# Lora_GPS_Shield_v1_3.net
KiCad netlist of a schematic drawn in EAGLE
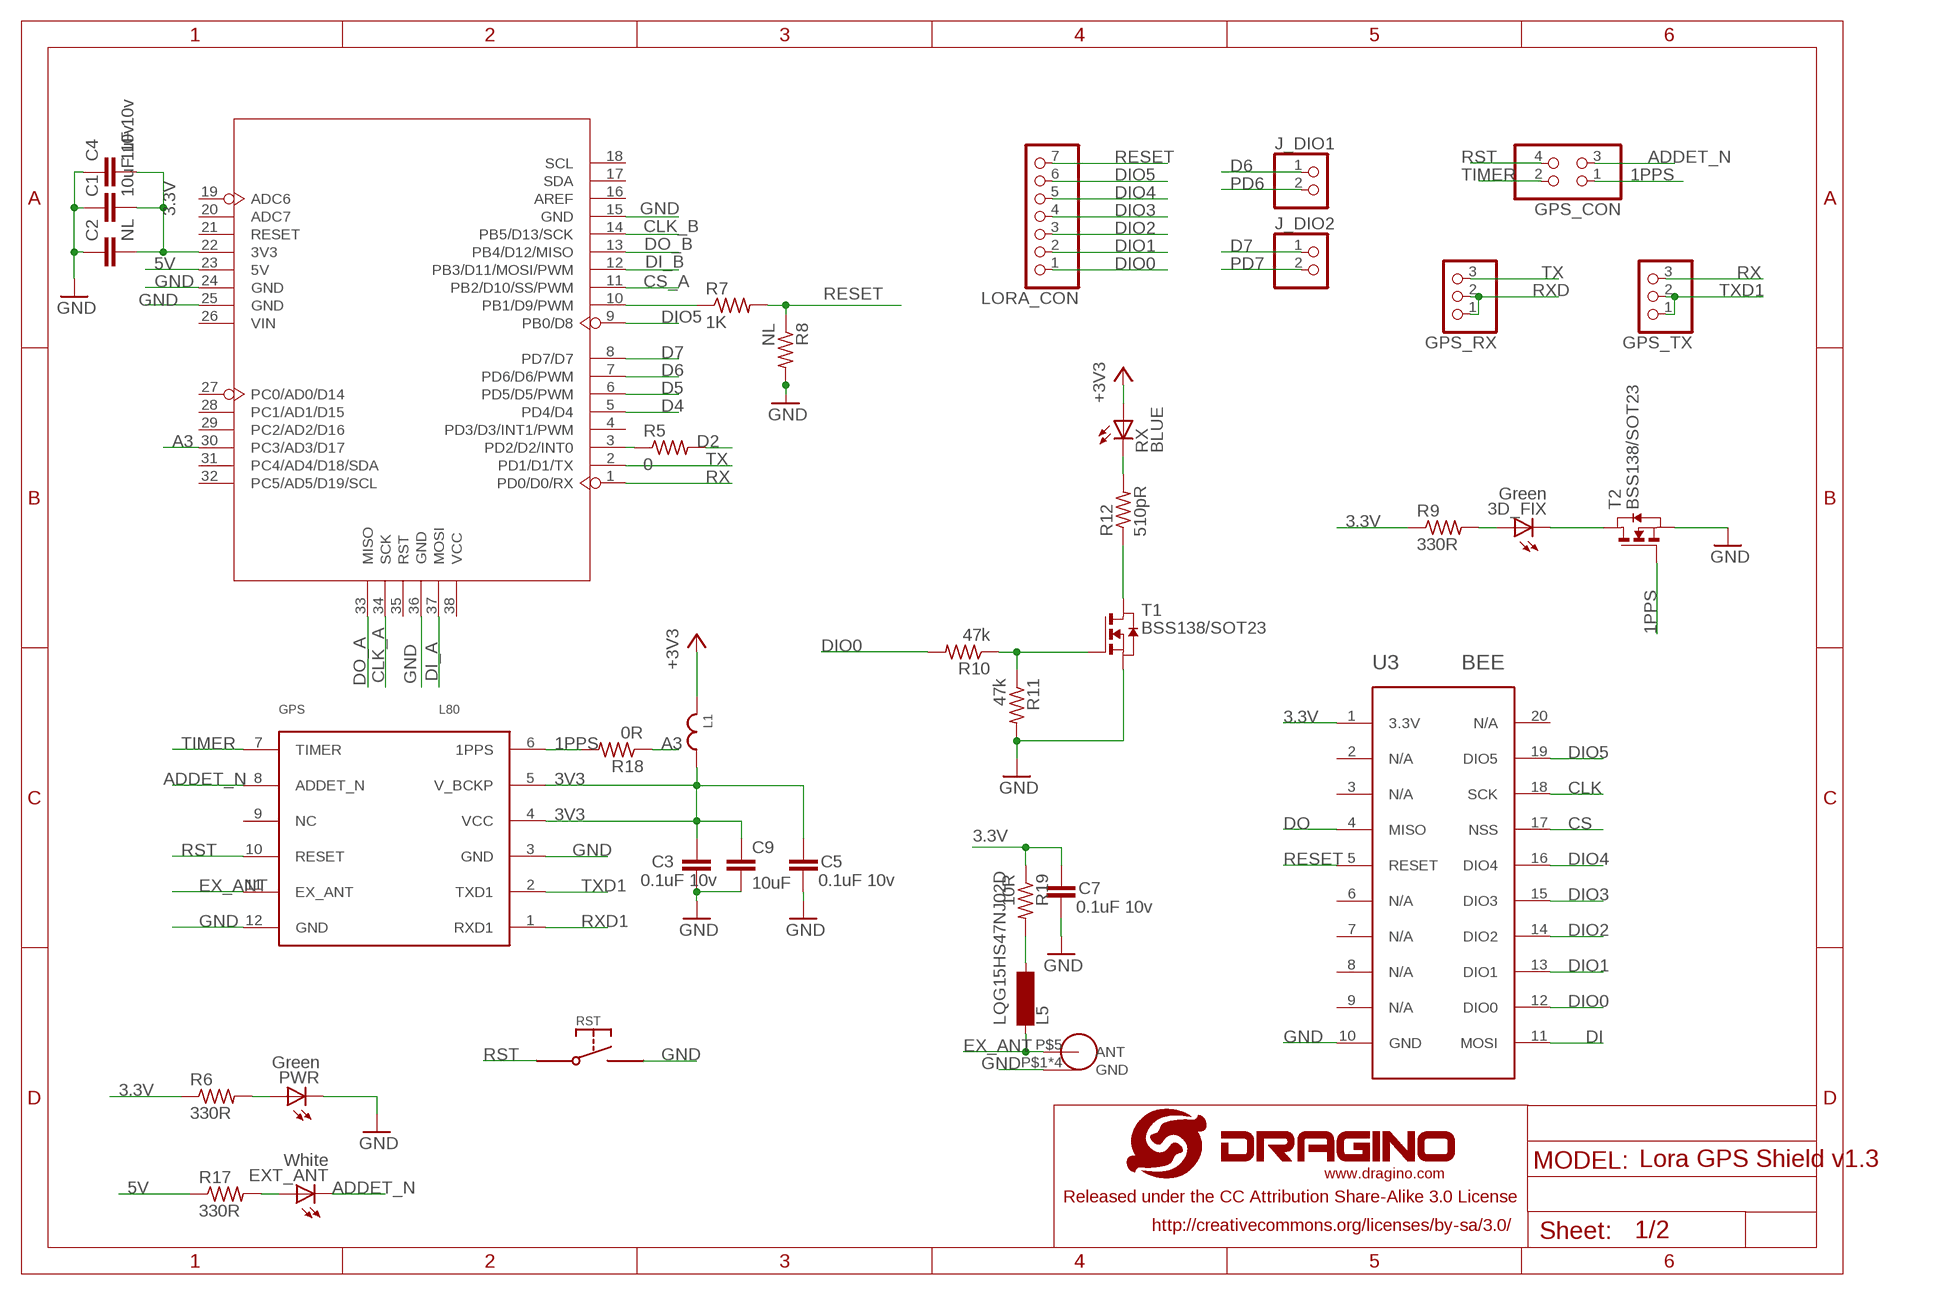
[diagram p0: schematic, sheet 1]
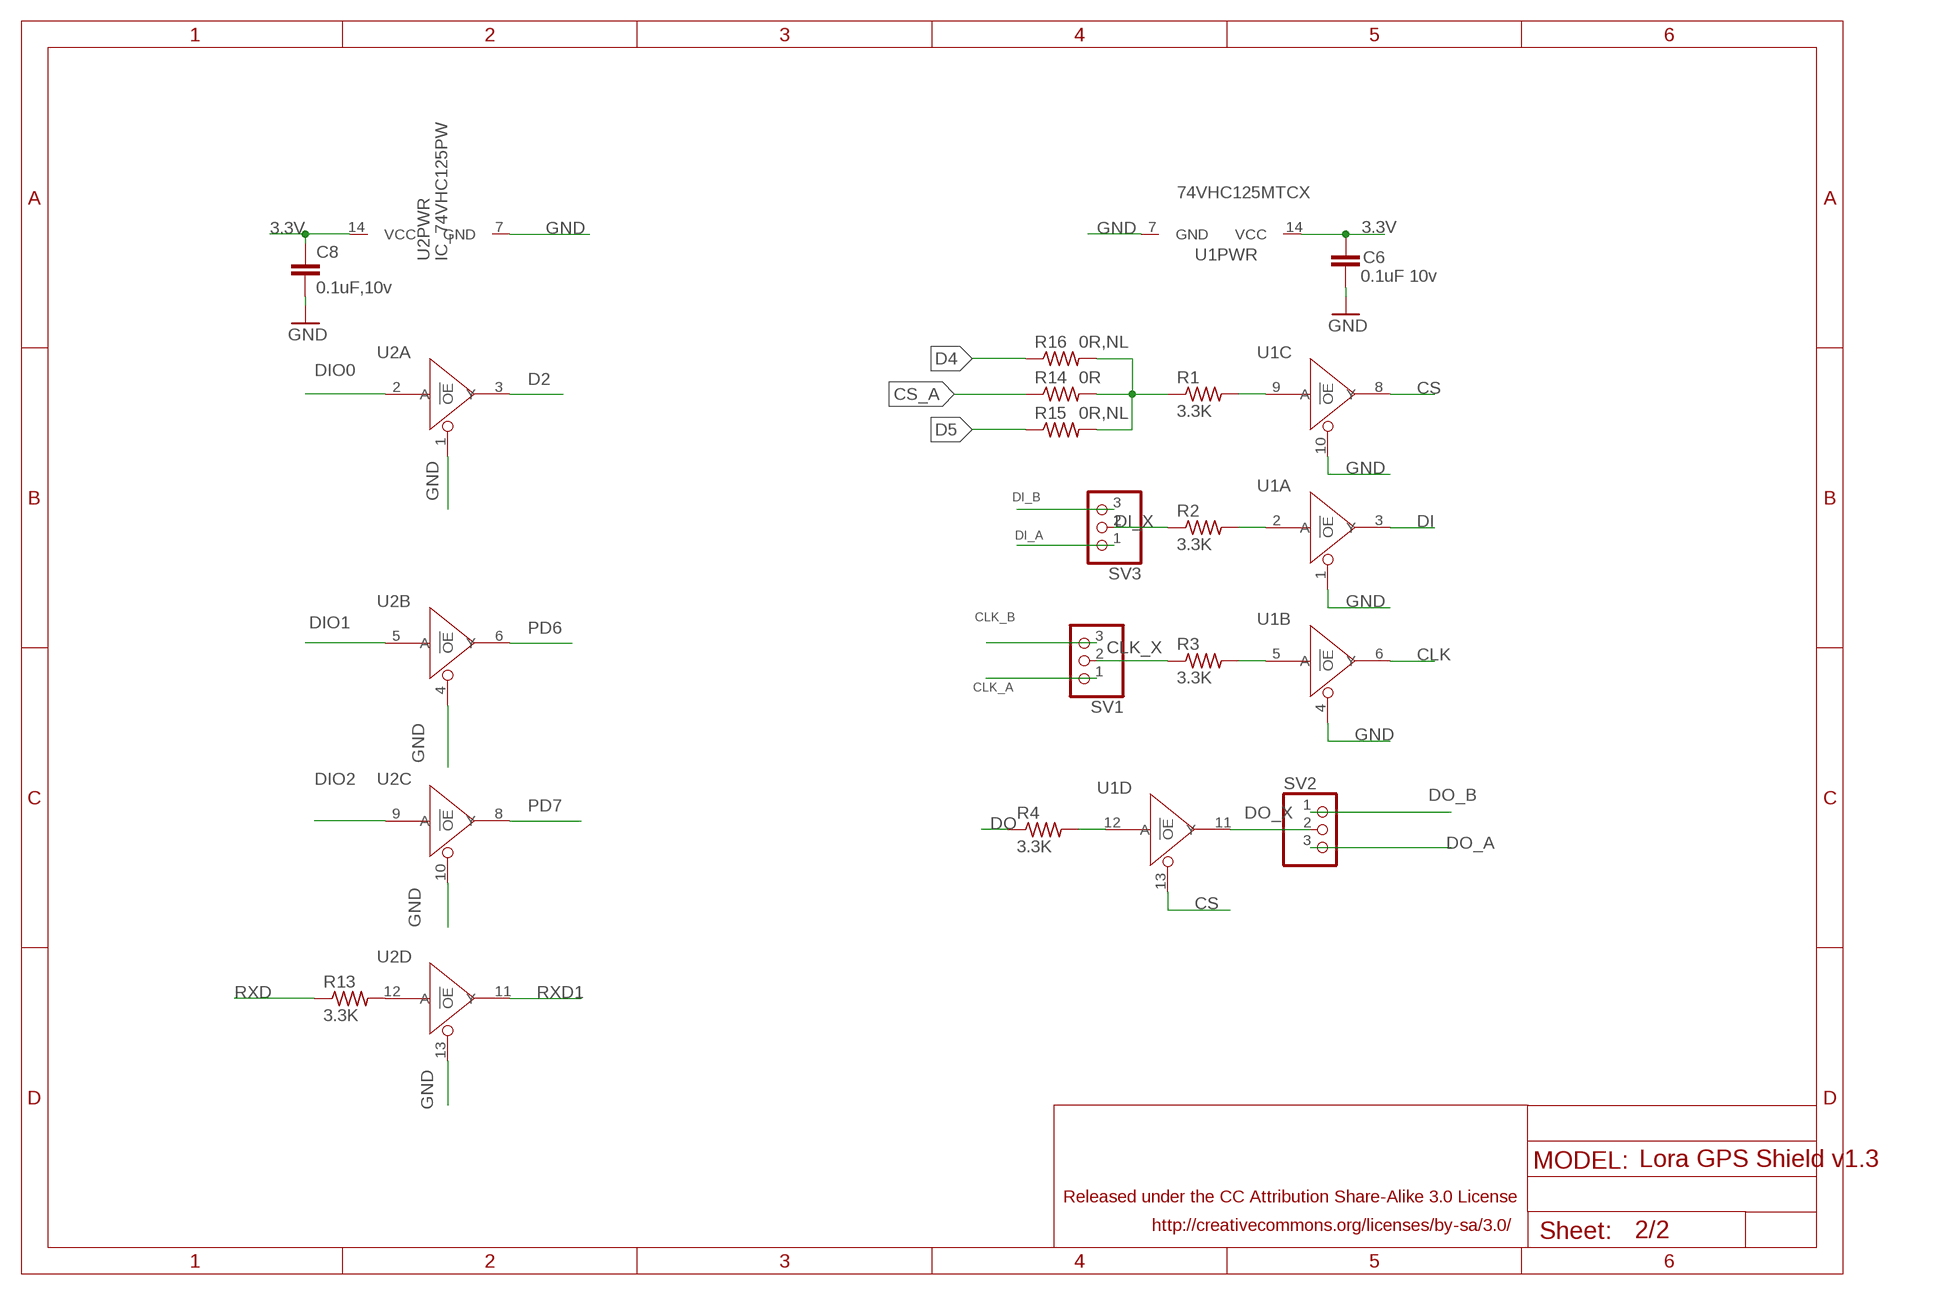
[diagram p1: schematic, sheet 2]

(export (version "E")
  (design (tool "Eeschema 10.0.6"))
  (components
    (comp (ref "C6")
      (value "0.1uF 10v")
      (footprint "eagle-import:C0402")
      (libsource (lib "eagle-import") (part "C-EUC0402"))
    )
    (comp (ref "C8")
      (value "0.1uF,10v")
      (footprint "eagle-import:C0402")
      (libsource (lib "eagle-import") (part "C-EUC0402"))
    )
    (comp (ref "R1")
      (value "3.3K")
      (footprint "eagle-import:R0402")
      (libsource (lib "eagle-import") (part "R-US_R0402"))
    )
    (comp (ref "R2")
      (value "3.3K")
      (footprint "eagle-import:R0402")
      (libsource (lib "eagle-import") (part "R-US_R0402"))
    )
    (comp (ref "R3")
      (value "3.3K")
      (footprint "eagle-import:R0402")
      (libsource (lib "eagle-import") (part "R-US_R0402"))
    )
    (comp (ref "R4")
      (value "3.3K")
      (footprint "eagle-import:R0402")
      (libsource (lib "eagle-import") (part "R-US_R0402"))
    )
    (comp (ref "R13")
      (value "3.3K")
      (footprint "eagle-import:R0402")
      (libsource (lib "eagle-import") (part "R-US_R0402"))
    )
    (comp (ref "R14")
      (value "0R")
      (footprint "eagle-import:R0603")
      (libsource (lib "eagle-import") (part "R-US_R0603"))
    )
    (comp (ref "R15")
      (value "0R,NL")
      (footprint "eagle-import:R0603")
      (libsource (lib "eagle-import") (part "R-US_R0603"))
    )
    (comp (ref "R16")
      (value "0R,NL")
      (footprint "eagle-import:R0603")
      (libsource (lib "eagle-import") (part "R-US_R0603"))
    )
    (comp (ref "SV1")
      (value "PINHD-1X31X3_S")
      (footprint "eagle-import:1X03")
      (libsource (lib "eagle-import") (part "PINHD-1X31X3_S"))
    )
    (comp (ref "SV2")
      (value "PINHD-1X3")
      (footprint "eagle-import:1X03")
      (libsource (lib "eagle-import") (part "PINHD-1X3"))
    )
    (comp (ref "SV3")
      (value "PINHD-1X3")
      (footprint "eagle-import:1X03")
      (libsource (lib "eagle-import") (part "PINHD-1X3"))
    )
    (comp (ref "U1")
      (value "74VHC125MTCX")
      (footprint "eagle-import:TSSOP14")
      (libsource (lib "eagle-import") (part "IC_74V125PWHC"))
    )
    (comp (ref "U2")
      (value "IC_74VHC125PW")
      (footprint "eagle-import:IC_TSSOP14")
      (libsource (lib "eagle-import") (part "IC_74V125PWHC"))
    )
    (comp (ref "3D_FIX")
      (value "Green")
      (footprint "eagle-import:CHIPLED_0603")
      (libsource (lib "eagle-import") (part "LEDCHIPLED_0603"))
    )
    (comp (ref "C1")
      (value "10uF 10v")
      (footprint "eagle-import:C0805")
      (libsource (lib "eagle-import") (part "C-EUC0805"))
    )
    (comp (ref "C2")
      (value "NL")
      (footprint "eagle-import:C0402")
      (libsource (lib "eagle-import") (part "C-EUC0402"))
    )
    (comp (ref "C3")
      (value "0.1uF 10v")
      (footprint "eagle-import:C0402")
      (libsource (lib "eagle-import") (part "C-EUC0402"))
    )
    (comp (ref "C4")
      (value "1uF 10v")
      (footprint "eagle-import:C0402")
      (libsource (lib "eagle-import") (part "C-EUC0402"))
    )
    (comp (ref "C5")
      (value "0.1uF 10v")
      (footprint "eagle-import:C0402")
      (libsource (lib "eagle-import") (part "C-EUC0402"))
    )
    (comp (ref "C7")
      (value "0.1uF 10v")
      (footprint "eagle-import:C0402")
      (libsource (lib "eagle-import") (part "C-EUC0402"))
    )
    (comp (ref "C9")
      (value "10uF")
      (footprint "eagle-import:C0805")
      (libsource (lib "eagle-import") (part "C-EUC0805"))
    )
    (comp (ref "EXT_ANT")
      (value "White")
      (footprint "eagle-import:DRAGINO_CHIPLED_0603")
      (libsource (lib "eagle-import") (part "DRAGINO_LEDCHIPLED_0603"))
    )
    (comp (ref "GPS")
      (value "L80")
      (footprint "eagle-import:L80")
      (libsource (lib "eagle-import") (part "L80"))
    )
    (comp (ref "GPS_ANT")
      (value "NL")
      (footprint "eagle-import:SMA-KE")
      (libsource (lib "eagle-import") (part "SMA-KE"))
    )
    (comp (ref "GPS_CON")
      (value "PINHD-2X2")
      (footprint "eagle-import:2X02")
      (libsource (lib "eagle-import") (part "PINHD-2X2"))
    )
    (comp (ref "GPS_RX")
      (value "PINHD-1X3")
      (footprint "eagle-import:1X03")
      (libsource (lib "eagle-import") (part "PINHD-1X3"))
    )
    (comp (ref "GPS_TX")
      (value "PINHD-1X3")
      (footprint "eagle-import:1X03")
      (libsource (lib "eagle-import") (part "PINHD-1X3"))
    )
    (comp (ref "J_DIO1")
      (value "PINHD-1X21X2_S")
      (footprint "eagle-import:1X02")
      (libsource (lib "eagle-import") (part "PINHD-1X21X2_S"))
    )
    (comp (ref "J_DIO2")
      (value "PINHD-1X2")
      (footprint "eagle-import:1X02")
      (libsource (lib "eagle-import") (part "PINHD-1X2"))
    )
    (comp (ref "L1")
      (value "JLC-PZ2012D800-3R0TF")
      (footprint "eagle-import:C0805")
      (libsource (lib "eagle-import") (part "BEADS0805"))
    )
    (comp (ref "L5")
      (value "LQG15HS47NJ02D")
      (footprint "eagle-import:L-0402")
      (libsource (lib "eagle-import") (part "L"))
    )
    (comp (ref "LORA_CON")
      (value "PINHD-1X71X7_S")
      (footprint "eagle-import:1X07")
      (libsource (lib "eagle-import") (part "PINHD-1X71X7_S"))
    )
    (comp (ref "PWR")
      (value "Green")
      (footprint "eagle-import:DRAGINO_CHIPLED_0603")
      (libsource (lib "eagle-import") (part "DRAGINO_LEDCHIPLED_0603"))
    )
    (comp (ref "R5")
      (value "0")
      (footprint "eagle-import:R0402")
      (libsource (lib "eagle-import") (part "R-US_R0402"))
    )
    (comp (ref "R6")
      (value "330R")
      (footprint "eagle-import:R0402")
      (libsource (lib "eagle-import") (part "R-US_R0402"))
    )
    (comp (ref "R7")
      (value "1K")
      (footprint "eagle-import:R0402")
      (libsource (lib "eagle-import") (part "R-US_R0402"))
    )
    (comp (ref "R8")
      (value "NL")
      (footprint "eagle-import:R0402")
      (libsource (lib "eagle-import") (part "R-US_R0402"))
    )
    (comp (ref "R9")
      (value "330R")
      (footprint "eagle-import:R0402")
      (libsource (lib "eagle-import") (part "R-US_R0402"))
    )
    (comp (ref "R10")
      (value "47k")
      (footprint "eagle-import:R0402")
      (libsource (lib "eagle-import") (part "R-US_R0402"))
    )
    (comp (ref "R11")
      (value "47k")
      (footprint "eagle-import:R0402")
      (libsource (lib "eagle-import") (part "R-US_R0402"))
    )
    (comp (ref "R12")
      (value "510pR")
      (footprint "eagle-import:R0402")
      (libsource (lib "eagle-import") (part "R-US_R0402"))
    )
    (comp (ref "R17")
      (value "330R")
      (footprint "eagle-import:R0402")
      (libsource (lib "eagle-import") (part "R-US_R0402"))
    )
    (comp (ref "R18")
      (value "0R")
      (footprint "eagle-import:M0805")
      (libsource (lib "eagle-import") (part "R-US_M0805"))
    )
    (comp (ref "R19")
      (value "10R")
      (footprint "eagle-import:R0402")
      (libsource (lib "eagle-import") (part "R-US_R0402"))
    )
    (comp (ref "RST")
      (value "SWITCHTS-017")
      (footprint "eagle-import:TS-017")
      (libsource (lib "eagle-import") (part "SWITCHTS-017"))
    )
    (comp (ref "RX")
      (value "BLUE")
      (footprint "eagle-import:CHIPLED_0603")
      (libsource (lib "eagle-import") (part "dragino-passive_LEDCHIPLED_0603"))
    )
    (comp (ref "T1")
      (value "BSS138/SOT23")
      (footprint "eagle-import:SOT-23")
      (libsource (lib "eagle-import") (part "NMOSFET-SOT23"))
    )
    (comp (ref "T2")
      (value "BSS138/SOT23")
      (footprint "eagle-import:SOT-23")
      (libsource (lib "eagle-import") (part "NMOSFET-SOT23"))
    )
    (comp (ref "U$1")
      (value "LOGO-NEW")
      (footprint "eagle-import:LOGO-SILK-NEW")
      (libsource (lib "eagle-import") (part "LOGO-NEW"))
    )
    (comp (ref "U3")
      (value "BEE")
      (footprint "eagle-import:LORA")
      (libsource (lib "eagle-import") (part "LORAHAT_S"))
    )
    (comp (ref "U5")
      (value "MOUDLE_ARDUINO-38PMOUDLE_ARDUINO-38P_L")
      (footprint "eagle-import:MOUDLE_ARDUINO-38P_L")
      (libsource (lib "eagle-import") (part "MOUDLE_ARDUINO-38PMOUDLE_ARDUINO-38P_L"))
    )
  )
  (nets
    (net (code "1") (name "1PPS") (class "Default")
      (node (ref "GPS") (pin "6") (pinfunction "1PPS_6") (pintype "bidirectional"))
      (node (ref "GPS_CON") (pin "1") (pinfunction "1_1") (pintype "passive"))
      (node (ref "R18") (pin "2") (pinfunction "2_2") (pintype "passive"))
      (node (ref "T2") (pin "3") (pinfunction "G_3") (pintype "passive"))
    )
    (net (code "2") (name "3.3V") (class "Default")
      (node (ref "C1") (pin "2") (pinfunction "2_2") (pintype "passive"))
      (node (ref "C2") (pin "2") (pinfunction "2_2") (pintype "passive"))
      (node (ref "C4") (pin "2") (pinfunction "2_2") (pintype "passive"))
      (node (ref "C6") (pin "2") (pinfunction "2_2") (pintype "passive"))
      (node (ref "C7") (pin "2") (pinfunction "2_2") (pintype "passive"))
      (node (ref "C8") (pin "1") (pinfunction "1_1") (pintype "passive"))
      (node (ref "L1") (pin "1") (pinfunction "P$1_1") (pintype "bidirectional"))
      (node (ref "R19") (pin "1") (pinfunction "1_1") (pintype "passive"))
      (node (ref "R6") (pin "1") (pinfunction "1_1") (pintype "passive"))
      (node (ref "R9") (pin "1") (pinfunction "1_1") (pintype "passive"))
      (node (ref "RX") (pin "A") (pinfunction "A_A") (pintype "passive"))
      (node (ref "U1") (pin "14") (pinfunction "VCC_14") (pintype "power_in"))
      (node (ref "U2") (pin "14") (pinfunction "VCC_14") (pintype "power_in"))
      (node (ref "U3") (pin "1") (pinfunction "3.3V_1") (pintype "bidirectional"))
      (node (ref "U5") (pin "22") (pinfunction "3V3_22") (pintype "bidirectional"))
    )
    (net (code "3") (name "3V3") (class "Default")
      (node (ref "C3") (pin "2") (pinfunction "2_2") (pintype "passive"))
      (node (ref "C5") (pin "2") (pinfunction "2_2") (pintype "passive"))
      (node (ref "C9") (pin "1") (pinfunction "1_1") (pintype "passive"))
      (node (ref "GPS") (pin "4") (pinfunction "VCC_4") (pintype "bidirectional"))
      (node (ref "GPS") (pin "5") (pinfunction "V_BCKP_5") (pintype "bidirectional"))
      (node (ref "L1") (pin "2") (pinfunction "P$2_2") (pintype "bidirectional"))
    )
    (net (code "4") (name "5V") (class "Default")
      (node (ref "R17") (pin "1") (pinfunction "1_1") (pintype "passive"))
      (node (ref "U5") (pin "23") (pinfunction "5V_23") (pintype "bidirectional"))
    )
    (net (code "5") (name "A3") (class "Default")
      (node (ref "R18") (pin "1") (pinfunction "1_1") (pintype "passive"))
      (node (ref "U5") (pin "30") (pinfunction "PC3/AD3/D17_30") (pintype "bidirectional"))
    )
    (net (code "6") (name "ADDET_N") (class "Default")
      (node (ref "EXT_ANT") (pin "C") (pinfunction "C_C") (pintype "passive"))
      (node (ref "GPS") (pin "8") (pinfunction "ADDET_N_8") (pintype "bidirectional"))
      (node (ref "GPS_CON") (pin "3") (pinfunction "3_3") (pintype "passive"))
    )
    (net (code "7") (name "CLK") (class "Default")
      (node (ref "U1") (pin "6") (pinfunction "Y_6") (pintype "bidirectional"))
      (node (ref "U3") (pin "18") (pinfunction "SCK_18") (pintype "bidirectional"))
    )
    (net (code "8") (name "CLK_A") (class "Default")
      (node (ref "SV1") (pin "1") (pinfunction "1_1") (pintype "passive"))
      (node (ref "U5") (pin "34") (pinfunction "SCK_34") (pintype "bidirectional"))
    )
    (net (code "9") (name "CLK_B") (class "Default")
      (node (ref "SV1") (pin "3") (pinfunction "3_3") (pintype "passive"))
      (node (ref "U5") (pin "14") (pinfunction "PB5/D13/SCK_14") (pintype "bidirectional"))
    )
    (net (code "10") (name "CLK_X") (class "Default")
      (node (ref "R3") (pin "1") (pinfunction "1_1") (pintype "passive"))
      (node (ref "SV1") (pin "2") (pinfunction "2_2") (pintype "passive"))
    )
    (net (code "11") (name "CS") (class "Default")
      (node (ref "U1") (pin "13") (pinfunction "~{OE}_13") (pintype "bidirectional"))
      (node (ref "U1") (pin "8") (pinfunction "Y_8") (pintype "bidirectional"))
      (node (ref "U3") (pin "17") (pinfunction "NSS_17") (pintype "bidirectional"))
    )
    (net (code "12") (name "CS_A") (class "Default")
      (node (ref "R14") (pin "1") (pinfunction "1_1") (pintype "passive"))
      (node (ref "U5") (pin "11") (pinfunction "PB2/D10/SS/PWM_11") (pintype "bidirectional"))
    )
    (net (code "13") (name "D2") (class "Default")
      (node (ref "R5") (pin "2") (pinfunction "2_2") (pintype "passive"))
      (node (ref "U2") (pin "3") (pinfunction "Y_3") (pintype "bidirectional"))
    )
    (net (code "14") (name "D4") (class "Default")
      (node (ref "R16") (pin "1") (pinfunction "1_1") (pintype "passive"))
      (node (ref "U5") (pin "5") (pinfunction "PD4/D4_5") (pintype "bidirectional"))
    )
    (net (code "15") (name "D5") (class "Default")
      (node (ref "R15") (pin "1") (pinfunction "1_1") (pintype "passive"))
      (node (ref "U5") (pin "6") (pinfunction "PD5/D5/PWM_6") (pintype "bidirectional"))
    )
    (net (code "16") (name "D6") (class "Default")
      (node (ref "J_DIO1") (pin "1") (pinfunction "1_1") (pintype "passive"))
      (node (ref "U5") (pin "7") (pinfunction "PD6/D6/PWM_7") (pintype "bidirectional"))
    )
    (net (code "17") (name "D7") (class "Default")
      (node (ref "J_DIO2") (pin "1") (pinfunction "1_1") (pintype "passive"))
      (node (ref "U5") (pin "8") (pinfunction "PD7/D7_8") (pintype "bidirectional"))
    )
    (net (code "18") (name "DI") (class "Default")
      (node (ref "U1") (pin "3") (pinfunction "Y_3") (pintype "bidirectional"))
      (node (ref "U3") (pin "11") (pinfunction "MOSI_11") (pintype "bidirectional"))
    )
    (net (code "19") (name "DIO0") (class "Default")
      (node (ref "LORA_CON") (pin "1") (pinfunction "1_1") (pintype "passive"))
      (node (ref "R10") (pin "2") (pinfunction "2_2") (pintype "passive"))
      (node (ref "U2") (pin "2") (pinfunction "A_2") (pintype "bidirectional"))
      (node (ref "U3") (pin "12") (pinfunction "DIO0_12") (pintype "bidirectional"))
    )
    (net (code "20") (name "DIO1") (class "Default")
      (node (ref "LORA_CON") (pin "2") (pinfunction "2_2") (pintype "passive"))
      (node (ref "U2") (pin "5") (pinfunction "A_5") (pintype "bidirectional"))
      (node (ref "U3") (pin "13") (pinfunction "DIO1_13") (pintype "bidirectional"))
    )
    (net (code "21") (name "DIO2") (class "Default")
      (node (ref "LORA_CON") (pin "3") (pinfunction "3_3") (pintype "passive"))
      (node (ref "U2") (pin "9") (pinfunction "A_9") (pintype "bidirectional"))
      (node (ref "U3") (pin "14") (pinfunction "DIO2_14") (pintype "bidirectional"))
    )
    (net (code "22") (name "DIO3") (class "Default")
      (node (ref "LORA_CON") (pin "4") (pinfunction "4_4") (pintype "passive"))
      (node (ref "U3") (pin "15") (pinfunction "DIO3_15") (pintype "bidirectional"))
    )
    (net (code "23") (name "DIO4") (class "Default")
      (node (ref "LORA_CON") (pin "5") (pinfunction "5_5") (pintype "passive"))
      (node (ref "U3") (pin "16") (pinfunction "DIO4_16") (pintype "bidirectional"))
    )
    (net (code "24") (name "DIO5") (class "Default")
      (node (ref "LORA_CON") (pin "6") (pinfunction "6_6") (pintype "passive"))
      (node (ref "U3") (pin "19") (pinfunction "DIO5_19") (pintype "bidirectional"))
      (node (ref "U5") (pin "9") (pinfunction "PB0/D8_9") (pintype "bidirectional"))
    )
    (net (code "25") (name "DI_A") (class "Default")
      (node (ref "SV3") (pin "1") (pinfunction "1_1") (pintype "passive"))
      (node (ref "U5") (pin "37") (pinfunction "MOSI_37") (pintype "bidirectional"))
    )
    (net (code "26") (name "DI_B") (class "Default")
      (node (ref "SV3") (pin "3") (pinfunction "3_3") (pintype "passive"))
      (node (ref "U5") (pin "12") (pinfunction "PB3/D11/MOSI/PWM_12") (pintype "bidirectional"))
    )
    (net (code "27") (name "DI_X") (class "Default")
      (node (ref "R2") (pin "1") (pinfunction "1_1") (pintype "passive"))
      (node (ref "SV3") (pin "2") (pinfunction "2_2") (pintype "passive"))
    )
    (net (code "28") (name "DO") (class "Default")
      (node (ref "R4") (pin "1") (pinfunction "1_1") (pintype "passive"))
      (node (ref "U3") (pin "4") (pinfunction "MISO_4") (pintype "bidirectional"))
    )
    (net (code "29") (name "DO_A") (class "Default")
      (node (ref "SV2") (pin "3") (pinfunction "3_3") (pintype "passive"))
      (node (ref "U5") (pin "33") (pinfunction "MISO_33") (pintype "bidirectional"))
    )
    (net (code "30") (name "DO_B") (class "Default")
      (node (ref "SV2") (pin "1") (pinfunction "1_1") (pintype "passive"))
      (node (ref "U5") (pin "13") (pinfunction "PB4/D12/MISO_13") (pintype "bidirectional"))
    )
    (net (code "31") (name "DO_X") (class "Default")
      (node (ref "SV2") (pin "2") (pinfunction "2_2") (pintype "passive"))
      (node (ref "U1") (pin "11") (pinfunction "Y_11") (pintype "bidirectional"))
    )
    (net (code "32") (name "EX_ANT") (class "Default")
      (node (ref "GPS") (pin "11") (pinfunction "EX_ANT_11") (pintype "bidirectional"))
      (node (ref "GPS_ANT") (pin "P$5") (pinfunction "ANT_P$5") (pintype "bidirectional"))
      (node (ref "L5") (pin "1") (pinfunction "1_1") (pintype "passive"))
    )
    (net (code "33") (name "GND") (class "Default")
      (node (ref "C1") (pin "1") (pinfunction "1_1") (pintype "passive"))
      (node (ref "C2") (pin "1") (pinfunction "1_1") (pintype "passive"))
      (node (ref "C3") (pin "1") (pinfunction "1_1") (pintype "passive"))
      (node (ref "C4") (pin "1") (pinfunction "1_1") (pintype "passive"))
      (node (ref "C5") (pin "1") (pinfunction "1_1") (pintype "passive"))
      (node (ref "C6") (pin "1") (pinfunction "1_1") (pintype "passive"))
      (node (ref "C7") (pin "1") (pinfunction "1_1") (pintype "passive"))
      (node (ref "C8") (pin "2") (pinfunction "2_2") (pintype "passive"))
      (node (ref "C9") (pin "2") (pinfunction "2_2") (pintype "passive"))
      (node (ref "GPS") (pin "12") (pinfunction "GND_12") (pintype "bidirectional"))
      (node (ref "GPS") (pin "3") (pinfunction "GND_3") (pintype "bidirectional"))
      (node (ref "GPS_ANT") (pin "P$1") (pinfunction "GND_P$1") (pintype "bidirectional"))
      (node (ref "GPS_ANT") (pin "P$2") (pinfunction "GND_P$2") (pintype "bidirectional"))
      (node (ref "GPS_ANT") (pin "P$3") (pinfunction "GND_P$3") (pintype "bidirectional"))
      (node (ref "GPS_ANT") (pin "P$4") (pinfunction "GND_P$4") (pintype "bidirectional"))
      (node (ref "PWR") (pin "C") (pinfunction "C_C") (pintype "passive"))
      (node (ref "R11") (pin "2") (pinfunction "2_2") (pintype "passive"))
      (node (ref "R8") (pin "2") (pinfunction "2_2") (pintype "passive"))
      (node (ref "RST") (pin "P$2") (pinfunction "P$2_P$2") (pintype "bidirectional"))
      (node (ref "T1") (pin "2") (pinfunction "S_2") (pintype "passive"))
      (node (ref "T2") (pin "2") (pinfunction "S_2") (pintype "passive"))
      (node (ref "U1") (pin "1") (pinfunction "~{OE}_1") (pintype "bidirectional"))
      (node (ref "U1") (pin "10") (pinfunction "~{OE}_10") (pintype "bidirectional"))
      (node (ref "U1") (pin "4") (pinfunction "~{OE}_4") (pintype "bidirectional"))
      (node (ref "U1") (pin "7") (pinfunction "GND_7") (pintype "power_in"))
      (node (ref "U2") (pin "1") (pinfunction "~{OE}_1") (pintype "bidirectional"))
      (node (ref "U2") (pin "10") (pinfunction "~{OE}_10") (pintype "bidirectional"))
      (node (ref "U2") (pin "13") (pinfunction "~{OE}_13") (pintype "bidirectional"))
      (node (ref "U2") (pin "4") (pinfunction "~{OE}_4") (pintype "bidirectional"))
      (node (ref "U2") (pin "7") (pinfunction "GND_7") (pintype "power_in"))
      (node (ref "U3") (pin "10") (pinfunction "GND_10") (pintype "bidirectional"))
      (node (ref "U5") (pin "15") (pinfunction "GND_15") (pintype "bidirectional"))
      (node (ref "U5") (pin "24") (pinfunction "GND_24") (pintype "bidirectional"))
      (node (ref "U5") (pin "25") (pinfunction "GND_25") (pintype "bidirectional"))
      (node (ref "U5") (pin "36") (pinfunction "GND_36") (pintype "bidirectional"))
    )
    (net (code "34") (name "Net-(3D_FIX-PadA)") (class "Default")
      (node (ref "3D_FIX") (pin "A") (pinfunction "A_A") (pintype "passive"))
      (node (ref "R9") (pin "2") (pinfunction "2_2") (pintype "passive"))
    )
    (net (code "35") (name "Net-(EXT_ANT-PadA)") (class "Default")
      (node (ref "EXT_ANT") (pin "A") (pinfunction "A_A") (pintype "passive"))
      (node (ref "R17") (pin "2") (pinfunction "2_2") (pintype "passive"))
    )
    (net (code "36") (name "Net-(L5-Pad2)") (class "Default")
      (node (ref "L5") (pin "2") (pinfunction "2_2") (pintype "passive"))
      (node (ref "R19") (pin "2") (pinfunction "2_2") (pintype "passive"))
    )
    (net (code "37") (name "Net-(PWR-PadA)") (class "Default")
      (node (ref "PWR") (pin "A") (pinfunction "A_A") (pintype "passive"))
      (node (ref "R6") (pin "2") (pinfunction "2_2") (pintype "passive"))
    )
    (net (code "38") (name "Net-(R1-Pad1)") (class "Default")
      (node (ref "R1") (pin "1") (pinfunction "1_1") (pintype "passive"))
      (node (ref "R14") (pin "2") (pinfunction "2_2") (pintype "passive"))
      (node (ref "R15") (pin "2") (pinfunction "2_2") (pintype "passive"))
      (node (ref "R16") (pin "2") (pinfunction "2_2") (pintype "passive"))
    )
    (net (code "39") (name "Net-(R12-Pad2)") (class "Default")
      (node (ref "R12") (pin "2") (pinfunction "2_2") (pintype "passive"))
      (node (ref "RX") (pin "C") (pinfunction "C_C") (pintype "passive"))
    )
    (net (code "40") (name "Net-(T1-D)") (class "Default")
      (node (ref "R12") (pin "1") (pinfunction "1_1") (pintype "passive"))
      (node (ref "T1") (pin "1") (pinfunction "D_1") (pintype "passive"))
    )
    (net (code "41") (name "Net-(T1-G)") (class "Default")
      (node (ref "R10") (pin "1") (pinfunction "1_1") (pintype "passive"))
      (node (ref "R11") (pin "1") (pinfunction "1_1") (pintype "passive"))
      (node (ref "T1") (pin "3") (pinfunction "G_3") (pintype "passive"))
    )
    (net (code "42") (name "Net-(T2-D)") (class "Default")
      (node (ref "3D_FIX") (pin "C") (pinfunction "C_C") (pintype "passive"))
      (node (ref "T2") (pin "1") (pinfunction "D_1") (pintype "passive"))
    )
    (net (code "43") (name "Net-(U1A-A)") (class "Default")
      (node (ref "R2") (pin "2") (pinfunction "2_2") (pintype "passive"))
      (node (ref "U1") (pin "2") (pinfunction "A_2") (pintype "bidirectional"))
    )
    (net (code "44") (name "Net-(U1B-A)") (class "Default")
      (node (ref "R3") (pin "2") (pinfunction "2_2") (pintype "passive"))
      (node (ref "U1") (pin "5") (pinfunction "A_5") (pintype "bidirectional"))
    )
    (net (code "45") (name "Net-(U1C-A)") (class "Default")
      (node (ref "R1") (pin "2") (pinfunction "2_2") (pintype "passive"))
      (node (ref "U1") (pin "9") (pinfunction "A_9") (pintype "bidirectional"))
    )
    (net (code "46") (name "Net-(U1D-A)") (class "Default")
      (node (ref "R4") (pin "2") (pinfunction "2_2") (pintype "passive"))
      (node (ref "U1") (pin "12") (pinfunction "A_12") (pintype "bidirectional"))
    )
    (net (code "47") (name "Net-(U2D-A)") (class "Default")
      (node (ref "R13") (pin "2") (pinfunction "2_2") (pintype "passive"))
      (node (ref "U2") (pin "12") (pinfunction "A_12") (pintype "bidirectional"))
    )
    (net (code "48") (name "Net-(U5-PB1{slash}D9{slash}PWM)") (class "Default")
      (node (ref "R7") (pin "1") (pinfunction "1_1") (pintype "passive"))
      (node (ref "U5") (pin "10") (pinfunction "PB1/D9/PWM_10") (pintype "bidirectional"))
    )
    (net (code "49") (name "Net-(U5-PD2{slash}D2{slash}INT0)") (class "Default")
      (node (ref "R5") (pin "1") (pinfunction "1_1") (pintype "passive"))
      (node (ref "U5") (pin "3") (pinfunction "PD2/D2/INT0_3") (pintype "bidirectional"))
    )
    (net (code "50") (name "PD6") (class "Default")
      (node (ref "J_DIO1") (pin "2") (pinfunction "2_2") (pintype "passive"))
      (node (ref "U2") (pin "6") (pinfunction "Y_6") (pintype "bidirectional"))
    )
    (net (code "51") (name "PD7") (class "Default")
      (node (ref "J_DIO2") (pin "2") (pinfunction "2_2") (pintype "passive"))
      (node (ref "U2") (pin "8") (pinfunction "Y_8") (pintype "bidirectional"))
    )
    (net (code "52") (name "RESET") (class "Default")
      (node (ref "LORA_CON") (pin "7") (pinfunction "7_7") (pintype "passive"))
      (node (ref "R7") (pin "2") (pinfunction "2_2") (pintype "passive"))
      (node (ref "R8") (pin "1") (pinfunction "1_1") (pintype "passive"))
      (node (ref "U3") (pin "5") (pinfunction "RESET_5") (pintype "bidirectional"))
    )
    (net (code "53") (name "RST") (class "Default")
      (node (ref "GPS") (pin "10") (pinfunction "RESET_10") (pintype "bidirectional"))
      (node (ref "GPS_CON") (pin "4") (pinfunction "4_4") (pintype "passive"))
      (node (ref "RST") (pin "P$1") (pinfunction "P$1_P$1") (pintype "bidirectional"))
    )
    (net (code "54") (name "RX") (class "Default")
      (node (ref "GPS_TX") (pin "3") (pinfunction "3_3") (pintype "passive"))
      (node (ref "U5") (pin "1") (pinfunction "PD0/D0/RX_1") (pintype "bidirectional"))
    )
    (net (code "55") (name "RXD") (class "Default")
      (node (ref "GPS_RX") (pin "1") (pinfunction "1_1") (pintype "passive"))
      (node (ref "GPS_RX") (pin "2") (pinfunction "2_2") (pintype "passive"))
      (node (ref "R13") (pin "1") (pinfunction "1_1") (pintype "passive"))
    )
    (net (code "56") (name "RXD1") (class "Default")
      (node (ref "GPS") (pin "1") (pinfunction "RXD1_1") (pintype "bidirectional"))
      (node (ref "U2") (pin "11") (pinfunction "Y_11") (pintype "bidirectional"))
    )
    (net (code "57") (name "TIMER") (class "Default")
      (node (ref "GPS") (pin "7") (pinfunction "TIMER_7") (pintype "bidirectional"))
      (node (ref "GPS_CON") (pin "2") (pinfunction "2_2") (pintype "passive"))
    )
    (net (code "58") (name "TX") (class "Default")
      (node (ref "GPS_RX") (pin "3") (pinfunction "3_3") (pintype "passive"))
      (node (ref "U5") (pin "2") (pinfunction "PD1/D1/TX_2") (pintype "bidirectional"))
    )
    (net (code "59") (name "TXD1") (class "Default")
      (node (ref "GPS") (pin "2") (pinfunction "TXD1_2") (pintype "bidirectional"))
      (node (ref "GPS_TX") (pin "1") (pinfunction "1_1") (pintype "passive"))
      (node (ref "GPS_TX") (pin "2") (pinfunction "2_2") (pintype "passive"))
    )
    (net (code "60") (name "unconnected-(GPS-NC-Pad9)") (class "Default")
      (node (ref "GPS") (pin "9") (pinfunction "NC_9") (pintype "bidirectional"))
    )
    (net (code "61") (name "unconnected-(U3-N{slash}A-Pad2)") (class "Default")
      (node (ref "U3") (pin "2") (pinfunction "N/A_2") (pintype "bidirectional"))
    )
    (net (code "62") (name "unconnected-(U3-N{slash}A-Pad3)") (class "Default")
      (node (ref "U3") (pin "3") (pinfunction "N/A_3") (pintype "bidirectional"))
    )
    (net (code "63") (name "unconnected-(U3-N{slash}A-Pad6)") (class "Default")
      (node (ref "U3") (pin "6") (pinfunction "N/A_6") (pintype "bidirectional"))
    )
    (net (code "64") (name "unconnected-(U3-N{slash}A-Pad7)") (class "Default")
      (node (ref "U3") (pin "7") (pinfunction "N/A_7") (pintype "bidirectional"))
    )
    (net (code "65") (name "unconnected-(U3-N{slash}A-Pad8)") (class "Default")
      (node (ref "U3") (pin "8") (pinfunction "N/A_8") (pintype "bidirectional"))
    )
    (net (code "66") (name "unconnected-(U3-N{slash}A-Pad9)") (class "Default")
      (node (ref "U3") (pin "9") (pinfunction "N/A_9") (pintype "bidirectional"))
    )
    (net (code "67") (name "unconnected-(U3-N{slash}A-Pad20)") (class "Default")
      (node (ref "U3") (pin "20") (pinfunction "N/A_20") (pintype "bidirectional"))
    )
    (net (code "68") (name "unconnected-(U5-ADC6-Pad19)") (class "Default")
      (node (ref "U5") (pin "19") (pinfunction "ADC6_19") (pintype "bidirectional"))
    )
    (net (code "69") (name "unconnected-(U5-ADC7-Pad20)") (class "Default")
      (node (ref "U5") (pin "20") (pinfunction "ADC7_20") (pintype "bidirectional"))
    )
    (net (code "70") (name "unconnected-(U5-AREF-Pad16)") (class "Default")
      (node (ref "U5") (pin "16") (pinfunction "AREF_16") (pintype "bidirectional"))
    )
    (net (code "71") (name "unconnected-(U5-PC0{slash}AD0{slash}D14-Pad27)") (class "Default")
      (node (ref "U5") (pin "27") (pinfunction "PC0/AD0/D14_27") (pintype "bidirectional"))
    )
    (net (code "72") (name "unconnected-(U5-PC1{slash}AD1{slash}D15-Pad28)") (class "Default")
      (node (ref "U5") (pin "28") (pinfunction "PC1/AD1/D15_28") (pintype "bidirectional"))
    )
    (net (code "73") (name "unconnected-(U5-PC2{slash}AD2{slash}D16-Pad29)") (class "Default")
      (node (ref "U5") (pin "29") (pinfunction "PC2/AD2/D16_29") (pintype "bidirectional"))
    )
    (net (code "74") (name "unconnected-(U5-PC4{slash}AD4{slash}D18{slash}SDA-Pad31)") (class "Default")
      (node (ref "U5") (pin "31") (pinfunction "PC4/AD4/D18/SDA_31") (pintype "bidirectional"))
    )
    (net (code "75") (name "unconnected-(U5-PC5{slash}AD5{slash}D19{slash}SCL-Pad32)") (class "Default")
      (node (ref "U5") (pin "32") (pinfunction "PC5/AD5/D19/SCL_32") (pintype "bidirectional"))
    )
    (net (code "76") (name "unconnected-(U5-PD3{slash}D3{slash}INT1{slash}PWM-Pad4)") (class "Default")
      (node (ref "U5") (pin "4") (pinfunction "PD3/D3/INT1/PWM_4") (pintype "bidirectional"))
    )
    (net (code "77") (name "unconnected-(U5-RESET-Pad21)") (class "Default")
      (node (ref "U5") (pin "21") (pinfunction "RESET_21") (pintype "bidirectional"))
    )
    (net (code "78") (name "unconnected-(U5-RST-Pad35)") (class "Default")
      (node (ref "U5") (pin "35") (pinfunction "RST_35") (pintype "bidirectional"))
    )
    (net (code "79") (name "unconnected-(U5-SCL-Pad18)") (class "Default")
      (node (ref "U5") (pin "18") (pinfunction "SCL_18") (pintype "bidirectional"))
    )
    (net (code "80") (name "unconnected-(U5-SDA-Pad17)") (class "Default")
      (node (ref "U5") (pin "17") (pinfunction "SDA_17") (pintype "bidirectional"))
    )
    (net (code "81") (name "unconnected-(U5-VCC-Pad38)") (class "Default")
      (node (ref "U5") (pin "38") (pinfunction "VCC_38") (pintype "bidirectional"))
    )
    (net (code "82") (name "unconnected-(U5-VIN-Pad26)") (class "Default")
      (node (ref "U5") (pin "26") (pinfunction "VIN_26") (pintype "bidirectional"))
    )
  )
)
